# Micro_Controller.net
KiCad netlist of a schematic drawn in Altium Designer
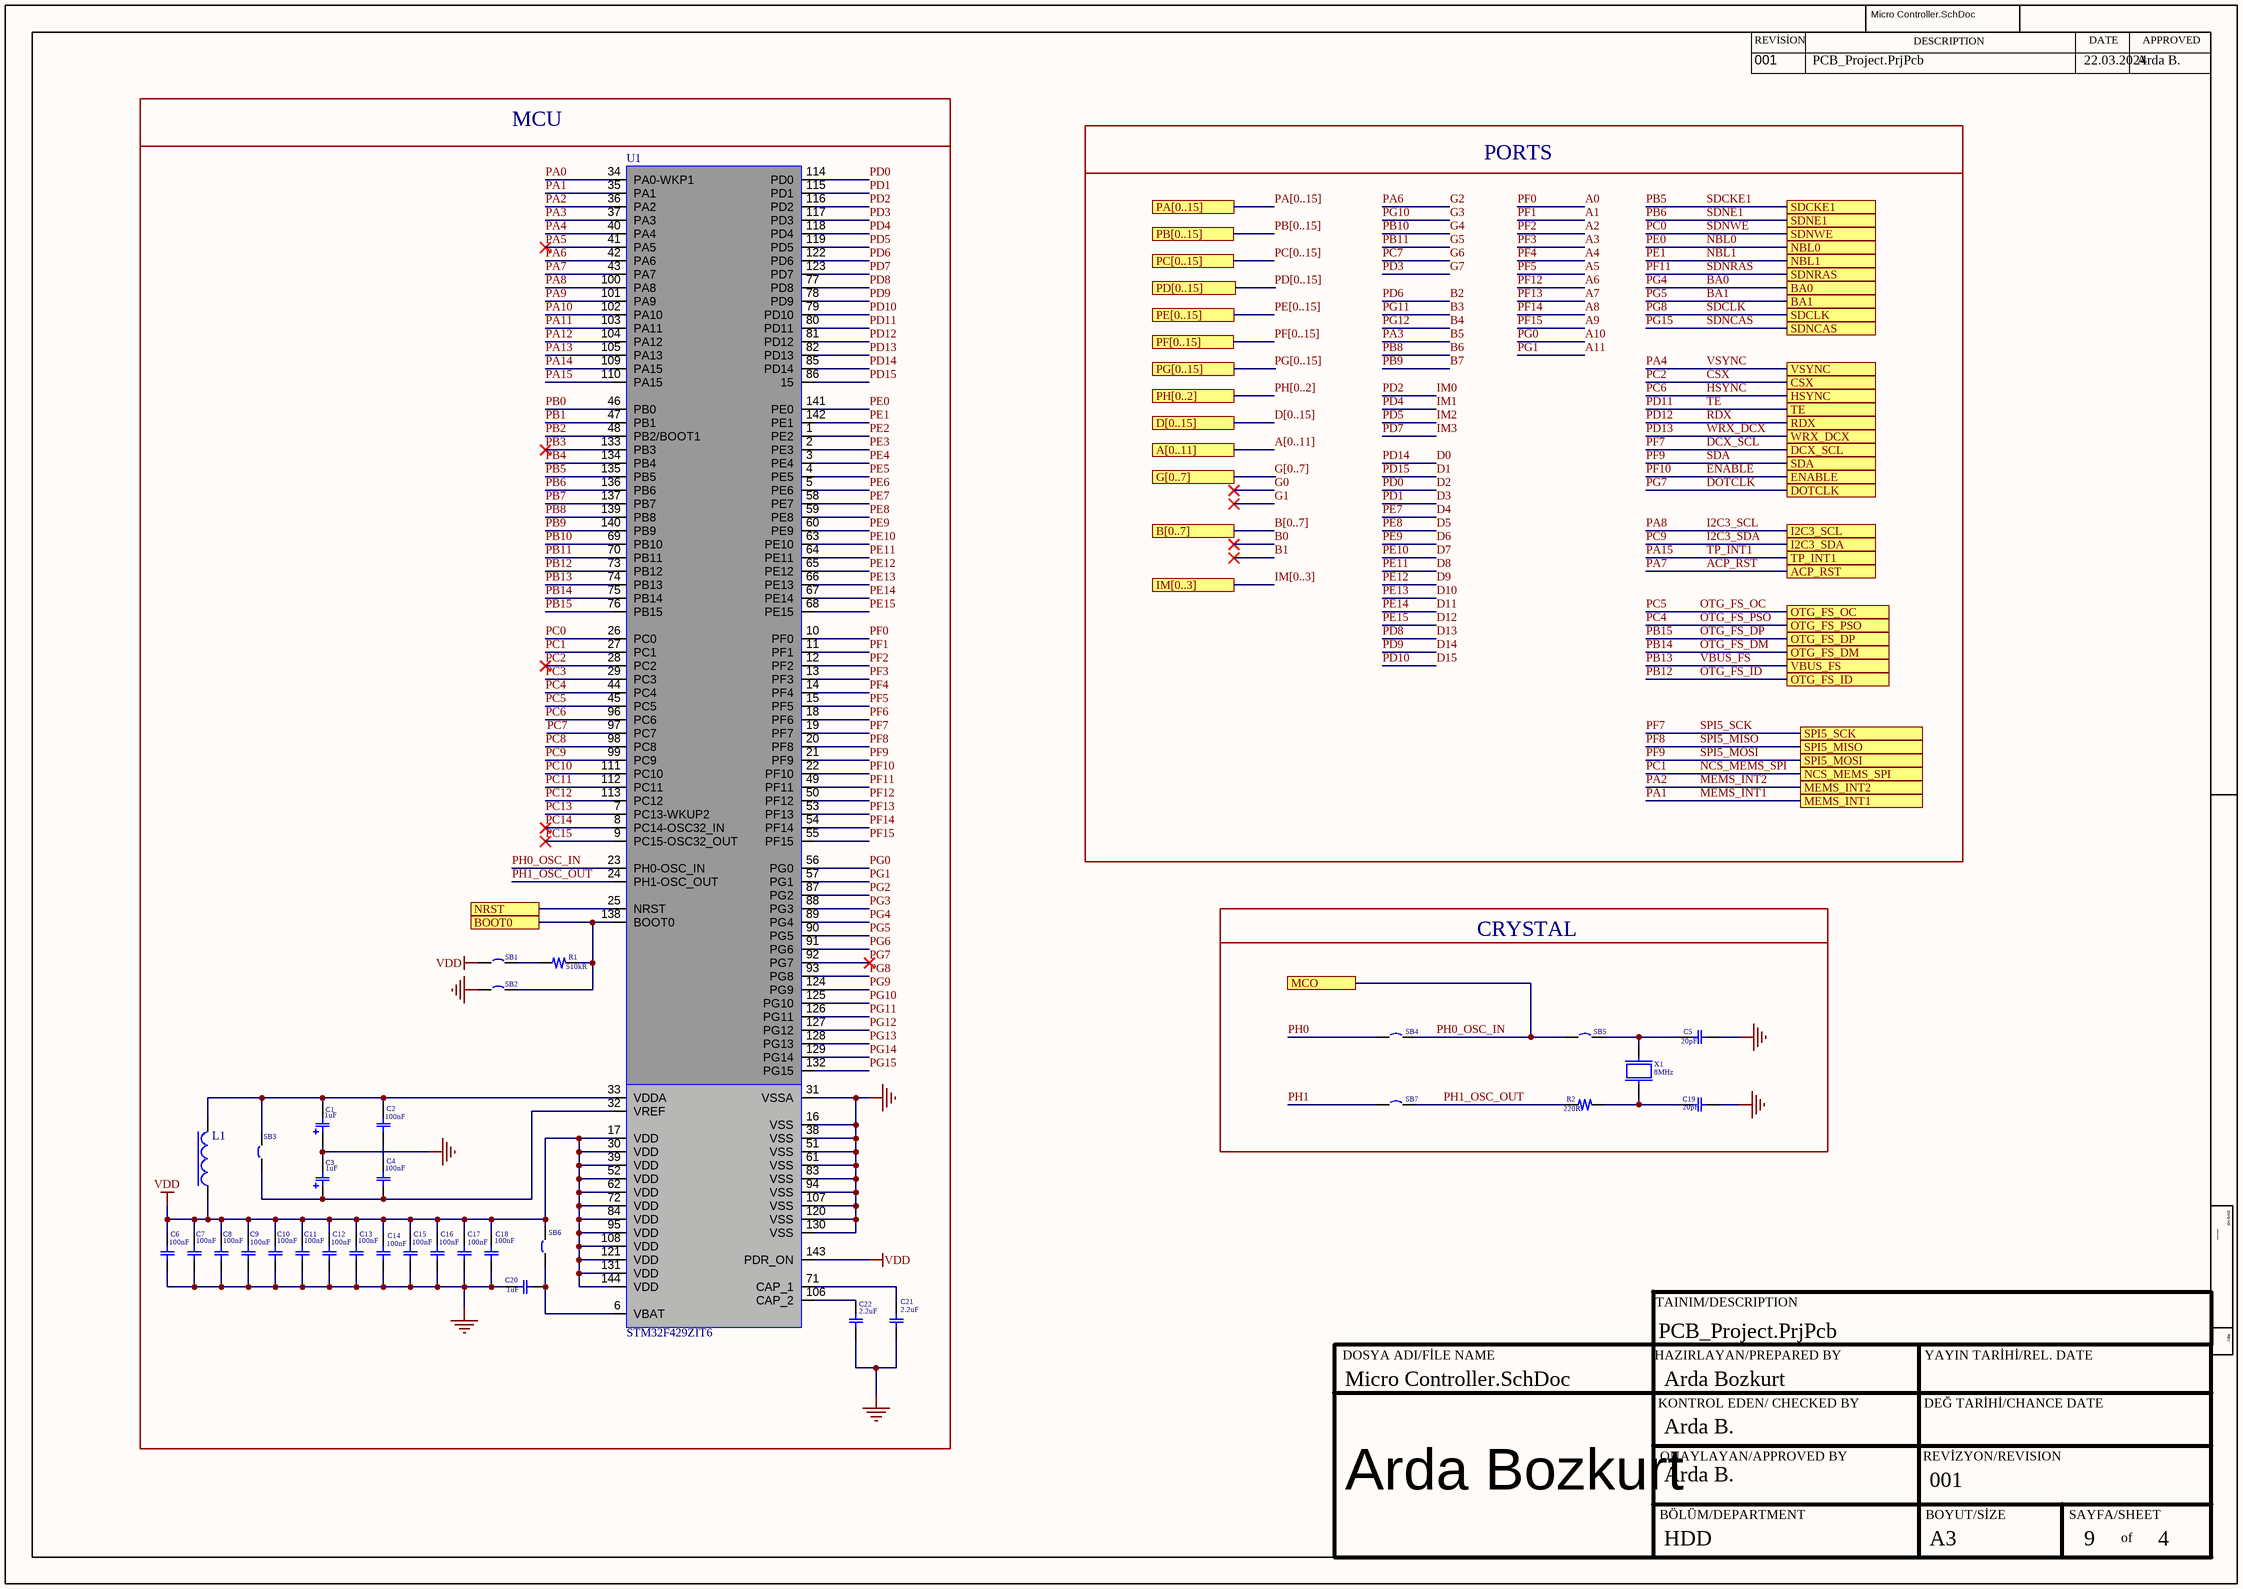
[diagram p0: Micro Controller.SchDoc]

(export (version "E")
  (design (tool "Eeschema 10.0.6"))
  (components
    (comp (ref "C1")
      (value "1uF")
      (footprint "CAP-TANT")
      (description "Cap Tant Solid 1uF 16V A CASE 10%( 3.2 X 1.6 X 1.6mm) Inward L SMD 3216-18 11 Ohm 125C T/R")
      (fields
        (field (name "MANUFACTURER") "Kyocera AVX")
        (field (name "MANUFACTURER PART NUMBER") "TAJA105K016RNJ")
      )
      (libsource (lib "STM32") (part "C-TANT 1UF 10% 16V 1206"))
    )
    (comp (ref "C2")
      (value "100nF")
      (footprint "CAP-0402")
      (description "Multilayer Ceramic Capacitor, 0.1 uF, 25 V, ± 10%, X7R, 0402 [1005 Metric]")
      (fields
        (field (name "MANUFACTURER") "Yageo")
        (field (name "MANUFACTURER PART NUMBER") "CC0402KRX7R7BB104")
      )
      (libsource (lib "STM32") (part "CAP CER 100nF 16V X7R 0402"))
    )
    (comp (ref "C3")
      (value "1uF")
      (footprint "CAP-TANT")
      (description "Cap Tant Solid 1uF 16V A CASE 10%( 3.2 X 1.6 X 1.6mm) Inward L SMD 3216-18 11 Ohm 125C T/R")
      (fields
        (field (name "MANUFACTURER") "Kyocera AVX")
        (field (name "MANUFACTURER PART NUMBER") "TAJA105K016RNJ")
      )
      (libsource (lib "STM32") (part "C-TANT 1UF 10% 16V 1206"))
    )
    (comp (ref "C4")
      (value "100nF")
      (footprint "CAP-0402")
      (description "Multilayer Ceramic Capacitor, 0.1 uF, 25 V, ± 10%, X7R, 0402 [1005 Metric]")
      (fields
        (field (name "MANUFACTURER") "Yageo")
        (field (name "MANUFACTURER PART NUMBER") "CC0402KRX7R7BB104")
      )
      (libsource (lib "STM32") (part "CAP CER 100nF 16V X7R 0402"))
    )
    (comp (ref "C5")
      (value "20pF")
      (footprint "CAP-0402")
      (description "CAP CER 20PF 50V C0G/NPO 0402")
      (fields
        (field (name "MANUFACTURER") "Yageo")
        (field (name "MANUFACTURER PART NUMBER") "CC0402JRNPO9BN200")
      )
      (libsource (lib "STM32") (part "CAP CER 20PF 50V C0G/NPO 0402"))
    )
    (comp (ref "C6")
      (value "100nF")
      (footprint "CAP-0402")
      (description "Multilayer Ceramic Capacitor, 0.1 uF, 25 V, ± 10%, X7R, 0402 [1005 Metric]")
      (fields
        (field (name "MANUFACTURER") "Yageo")
        (field (name "MANUFACTURER PART NUMBER") "CC0402KRX7R7BB104")
      )
      (libsource (lib "STM32") (part "CAP CER 100nF 16V X7R 0402"))
    )
    (comp (ref "C7")
      (value "100nF")
      (footprint "CAP-0402")
      (description "Multilayer Ceramic Capacitor, 0.1 uF, 25 V, ± 10%, X7R, 0402 [1005 Metric]")
      (fields
        (field (name "MANUFACTURER") "Yageo")
        (field (name "MANUFACTURER PART NUMBER") "CC0402KRX7R7BB104")
      )
      (libsource (lib "STM32") (part "CAP CER 100nF 16V X7R 0402"))
    )
    (comp (ref "C8")
      (value "100nF")
      (footprint "CAP-0402")
      (description "Multilayer Ceramic Capacitor, 0.1 uF, 25 V, ± 10%, X7R, 0402 [1005 Metric]")
      (fields
        (field (name "MANUFACTURER") "Yageo")
        (field (name "MANUFACTURER PART NUMBER") "CC0402KRX7R7BB104")
      )
      (libsource (lib "STM32") (part "CAP CER 100nF 16V X7R 0402"))
    )
    (comp (ref "C9")
      (value "100nF")
      (footprint "CAP-0402")
      (description "Multilayer Ceramic Capacitor, 0.1 uF, 25 V, ± 10%, X7R, 0402 [1005 Metric]")
      (fields
        (field (name "MANUFACTURER") "Yageo")
        (field (name "MANUFACTURER PART NUMBER") "CC0402KRX7R7BB104")
      )
      (libsource (lib "STM32") (part "CAP CER 100nF 16V X7R 0402"))
    )
    (comp (ref "C10")
      (value "100nF")
      (footprint "CAP-0402")
      (description "Multilayer Ceramic Capacitor, 0.1 uF, 25 V, ± 10%, X7R, 0402 [1005 Metric]")
      (fields
        (field (name "MANUFACTURER") "Yageo")
        (field (name "MANUFACTURER PART NUMBER") "CC0402KRX7R7BB104")
      )
      (libsource (lib "STM32") (part "CAP CER 100nF 16V X7R 0402"))
    )
    (comp (ref "C11")
      (value "100nF")
      (footprint "CAP-0402")
      (description "Multilayer Ceramic Capacitor, 0.1 uF, 25 V, ± 10%, X7R, 0402 [1005 Metric]")
      (fields
        (field (name "MANUFACTURER") "Yageo")
        (field (name "MANUFACTURER PART NUMBER") "CC0402KRX7R7BB104")
      )
      (libsource (lib "STM32") (part "CAP CER 100nF 16V X7R 0402"))
    )
    (comp (ref "C12")
      (value "100nF")
      (footprint "CAP-0402")
      (description "Multilayer Ceramic Capacitor, 0.1 uF, 25 V, ± 10%, X7R, 0402 [1005 Metric]")
      (fields
        (field (name "MANUFACTURER") "Yageo")
        (field (name "MANUFACTURER PART NUMBER") "CC0402KRX7R7BB104")
      )
      (libsource (lib "STM32") (part "CAP CER 100nF 16V X7R 0402"))
    )
    (comp (ref "C13")
      (value "100nF")
      (footprint "CAP-0402")
      (description "Multilayer Ceramic Capacitor, 0.1 uF, 25 V, ± 10%, X7R, 0402 [1005 Metric]")
      (fields
        (field (name "MANUFACTURER") "Yageo")
        (field (name "MANUFACTURER PART NUMBER") "CC0402KRX7R7BB104")
      )
      (libsource (lib "STM32") (part "CAP CER 100nF 16V X7R 0402"))
    )
    (comp (ref "C14")
      (value "100nF")
      (footprint "CAP-0402")
      (description "Multilayer Ceramic Capacitor, 0.1 uF, 25 V, ± 10%, X7R, 0402 [1005 Metric]")
      (fields
        (field (name "MANUFACTURER") "Yageo")
        (field (name "MANUFACTURER PART NUMBER") "CC0402KRX7R7BB104")
      )
      (libsource (lib "STM32") (part "CAP CER 100nF 16V X7R 0402"))
    )
    (comp (ref "C15")
      (value "100nF")
      (footprint "CAP-0402")
      (description "Multilayer Ceramic Capacitor, 0.1 uF, 25 V, ± 10%, X7R, 0402 [1005 Metric]")
      (fields
        (field (name "MANUFACTURER") "Yageo")
        (field (name "MANUFACTURER PART NUMBER") "CC0402KRX7R7BB104")
      )
      (libsource (lib "STM32") (part "CAP CER 100nF 16V X7R 0402"))
    )
    (comp (ref "C16")
      (value "100nF")
      (footprint "CAP-0402")
      (description "Multilayer Ceramic Capacitor, 0.1 uF, 25 V, ± 10%, X7R, 0402 [1005 Metric]")
      (fields
        (field (name "MANUFACTURER") "Yageo")
        (field (name "MANUFACTURER PART NUMBER") "CC0402KRX7R7BB104")
      )
      (libsource (lib "STM32") (part "CAP CER 100nF 16V X7R 0402"))
    )
    (comp (ref "C17")
      (value "100nF")
      (footprint "CAP-0402")
      (description "Multilayer Ceramic Capacitor, 0.1 uF, 25 V, ± 10%, X7R, 0402 [1005 Metric]")
      (fields
        (field (name "MANUFACTURER") "Yageo")
        (field (name "MANUFACTURER PART NUMBER") "CC0402KRX7R7BB104")
      )
      (libsource (lib "STM32") (part "CAP CER 100nF 16V X7R 0402"))
    )
    (comp (ref "C18")
      (value "100nF")
      (footprint "CAP-0402")
      (description "Multilayer Ceramic Capacitor, 0.1 uF, 25 V, ± 10%, X7R, 0402 [1005 Metric]")
      (fields
        (field (name "MANUFACTURER") "Yageo")
        (field (name "MANUFACTURER PART NUMBER") "CC0402KRX7R7BB104")
      )
      (libsource (lib "STM32") (part "CAP CER 100nF 16V X7R 0402"))
    )
    (comp (ref "C19")
      (value "20pF")
      (footprint "CAP-0402")
      (description "CAP CER 20PF 50V C0G/NPO 0402")
      (fields
        (field (name "MANUFACTURER") "Yageo")
        (field (name "MANUFACTURER PART NUMBER") "CC0402JRNPO9BN200")
      )
      (libsource (lib "STM32") (part "CAP CER 20PF 50V C0G/NPO 0402"))
    )
    (comp (ref "C20")
      (value "1uF")
      (footprint "CAP-0603")
      (description "Multilayer Ceramic Capacitor, 1 uF, 25 V, ± 10%, X5R, 0603 [1608 Metric]")
      (fields
        (field (name "MANUFACTURER") "Yageo")
        (field (name "MANUFACTURER PART NUMBER") "CC0603KRX5R8BB105")
      )
      (libsource (lib "STM32") (part "CAP CER 1UF 25V X5R 0603"))
    )
    (comp (ref "C21")
      (value "2.2uF")
      (footprint "CAP-1206")
      (description "Surface Mount Ceramic Multilayer Capacitor 2.2uF 10% X7R 16V 1206 Blister T/R")
      (fields
        (field (name "MANUFACTURER") "Yageo")
        (field (name "MANUFACTURER PART NUMBER") "CC1206KKX7R7BB225")
      )
      (libsource (lib "STM32") (part "CAP CER 2.2UF 16V X7R 1206"))
    )
    (comp (ref "C22")
      (value "2.2uF")
      (footprint "CAP-1206")
      (description "Surface Mount Ceramic Multilayer Capacitor 2.2uF 10% X7R 16V 1206 Blister T/R")
      (fields
        (field (name "MANUFACTURER") "Yageo")
        (field (name "MANUFACTURER PART NUMBER") "CC1206KKX7R7BB225")
      )
      (libsource (lib "STM32") (part "CAP CER 2.2UF 16V X7R 1206"))
    )
    (comp (ref "L1")
      (value "FCM 1608KF-301T05")
      (footprint "FB-0603")
      (description "500mA 1 350mΩ 300Ω@100MHz ±25% 0603 Ferrite Beads ROHS")
      (fields
        (field (name "MANUFACTURER") "Tai Tech")
        (field (name "MANUFACTURER PART NUMBER") "FCM1608KF-301T05")
      )
      (libsource (lib "STM32") (part "FB 300 OHMS @ 100 MHZ 1 POWER, SIGN"))
    )
    (comp (ref "R1")
      (value "510kR")
      (footprint "RES-0402")
      (description "SMD Chip Resistor, 510 kOhm, ± 1%, 63 mW, 0402 [1005 Metric], Thick Film, General Purpose")
      (fields
        (field (name "MANUFACTURER") "Yageo")
        (field (name "MANUFACTURER PART NUMBER") "RC0402FR-07510KL")
      )
      (libsource (lib "STM32") (part "RES 510K OHM 1% 1/16W 0402"))
    )
    (comp (ref "R2")
      (value "220R")
      (footprint "RES-0402")
      (description "SMD Chip Resistor, 220 Ohm, ± 1%, 63 mW, 0402 [1005 Metric], Thick Film, General Purpose")
      (fields
        (field (name "MANUFACTURER") "Yageo")
        (field (name "MANUFACTURER PART NUMBER") "RC0402FR-07220RL")
      )
      (libsource (lib "STM32") (part "RES 220 OHM 1% 1/16W 0402"))
    )
    (comp (ref "SB1")
      (value "RC0402JR-070RL")
      (footprint "RES-0402")
      (description "Zero Ohm Resistor, Jumper, 0402 [1005 Metric], Thick Film, 62.5 mW, 1 A, Surface Mount")
      (fields
        (field (name "MANUFACTURER") "Yageo")
        (field (name "MANUFACTURER PART NUMBER") "RC0603JR-070RL")
      )
      (libsource (lib "STM32") (part "RES 0 OHM JUMPER 1/10W 0603"))
    )
    (comp (ref "SB2")
      (value "RC0402JR-070RL")
      (footprint "RES-0402")
      (description "Zero Ohm Resistor, Jumper, 0402 [1005 Metric], Thick Film, 62.5 mW, 1 A, Surface Mount")
      (fields
        (field (name "MANUFACTURER") "Yageo")
        (field (name "MANUFACTURER PART NUMBER") "RC0603JR-070RL")
      )
      (libsource (lib "STM32") (part "RES 0 OHM JUMPER 1/10W 0603"))
    )
    (comp (ref "SB3")
      (value "RC0402JR-070RL")
      (footprint "RES-0402")
      (description "Zero Ohm Resistor, Jumper, 0402 [1005 Metric], Thick Film, 62.5 mW, 1 A, Surface Mount")
      (fields
        (field (name "MANUFACTURER") "Yageo")
        (field (name "MANUFACTURER PART NUMBER") "RC0603JR-070RL")
      )
      (libsource (lib "") (part "RES 0 OHM JUMPER 1/10W 0603_1"))
    )
    (comp (ref "SB4")
      (value "RC0402JR-070RL")
      (footprint "RES-0402")
      (description "Zero Ohm Resistor, Jumper, 0402 [1005 Metric], Thick Film, 62.5 mW, 1 A, Surface Mount")
      (fields
        (field (name "MANUFACTURER") "Yageo")
        (field (name "MANUFACTURER PART NUMBER") "RC0603JR-070RL")
      )
      (libsource (lib "STM32") (part "RES 0 OHM JUMPER 1/10W 0603"))
    )
    (comp (ref "SB5")
      (value "RC0402JR-070RL")
      (footprint "RES-0402")
      (description "Zero Ohm Resistor, Jumper, 0402 [1005 Metric], Thick Film, 62.5 mW, 1 A, Surface Mount")
      (fields
        (field (name "MANUFACTURER") "Yageo")
        (field (name "MANUFACTURER PART NUMBER") "RC0603JR-070RL")
      )
      (libsource (lib "STM32") (part "RES 0 OHM JUMPER 1/10W 0603"))
    )
    (comp (ref "SB6")
      (value "RC0402JR-070RL")
      (footprint "RES-0402")
      (description "Zero Ohm Resistor, Jumper, 0402 [1005 Metric], Thick Film, 62.5 mW, 1 A, Surface Mount")
      (fields
        (field (name "MANUFACTURER") "Yageo")
        (field (name "MANUFACTURER PART NUMBER") "RC0603JR-070RL")
      )
      (libsource (lib "") (part "RES 0 OHM JUMPER 1/10W 0603_1"))
    )
    (comp (ref "SB7")
      (value "RC0402JR-070RL")
      (footprint "RES-0402")
      (description "Zero Ohm Resistor, Jumper, 0402 [1005 Metric], Thick Film, 62.5 mW, 1 A, Surface Mount")
      (fields
        (field (name "MANUFACTURER") "Yageo")
        (field (name "MANUFACTURER PART NUMBER") "RC0603JR-070RL")
      )
      (libsource (lib "STM32") (part "RES 0 OHM JUMPER 1/10W 0603"))
    )
    (comp (ref "U1")
      (value "STM32F429ZIT6")
      (footprint "LQFP-144")
      (description "RISC Microcontroller, 32-Bit, FLASH, CORTEX-M4F CPU, 180MHz, CMOS, PQFP144")
      (fields (field (name "MANUFACTURER") "STMicroelectronics"))
      (libsource (lib "STM32") (part "IC MCU 32BIT 2MB FLASH 144LQFP"))
    )
    (comp (ref "X1")
      (value "H1OED8K5SC-112YXC-8M")
      (footprint "HC-49US")
      (description "HC-49US 8MHZ 20PF 20PPM H1OED8K5")
      (fields (field (name "MANUFACTURER") "YXC") (field (name "FREQUENCY") "8MHz"))
      (libsource (lib "STM32") (part "Crystal 8MHZ 20PF 20PPM H1OED8K5"))
    )
  )
  (nets
    (net (code "5") (name "/B2") (class "Default")
      (node (ref "U1") (pin "122") (pinfunction "PD6_122") (pintype "passive"))
    )
    (net (code "6") (name "/B3") (class "Default")
      (node (ref "U1") (pin "126") (pinfunction "PG11_126") (pintype "passive"))
    )
    (net (code "7") (name "/B4") (class "Default")
      (node (ref "U1") (pin "127") (pinfunction "PG12_127") (pintype "passive"))
    )
    (net (code "8") (name "/BOOT0") (class "Default")
      (node (ref "R1") (pin "2") (pinfunction "2_2") (pintype "passive"))
      (node (ref "SB2") (pin "2") (pinfunction "2_2") (pintype "passive"))
      (node (ref "U1") (pin "138") (pinfunction "BOOT0_138") (pintype "passive"))
    )
    (net (code "10") (name "/D0") (class "Default")
      (node (ref "U1") (pin "85") (pinfunction "PD14_85") (pintype "passive"))
    )
    (net (code "11") (name "/D1") (class "Default")
      (node (ref "U1") (pin "86") (pinfunction "15_86") (pintype "passive"))
    )
    (net (code "12") (name "/D2") (class "Default")
      (node (ref "U1") (pin "114") (pinfunction "PD0_114") (pintype "passive"))
    )
    (net (code "13") (name "/D3") (class "Default")
      (node (ref "U1") (pin "115") (pinfunction "PD1_115") (pintype "passive"))
    )
    (net (code "14") (name "/D4") (class "Default")
      (node (ref "U1") (pin "58") (pinfunction "PE7_58") (pintype "passive"))
    )
    (net (code "15") (name "/D5") (class "Default")
      (node (ref "U1") (pin "59") (pinfunction "PE8_59") (pintype "passive"))
    )
    (net (code "16") (name "/D6") (class "Default")
      (node (ref "U1") (pin "60") (pinfunction "PE9_60") (pintype "passive"))
    )
    (net (code "17") (name "/D7") (class "Default")
      (node (ref "U1") (pin "63") (pinfunction "PE10_63") (pintype "passive"))
    )
    (net (code "18") (name "/D8") (class "Default")
      (node (ref "U1") (pin "64") (pinfunction "PE11_64") (pintype "passive"))
    )
    (net (code "19") (name "/D9") (class "Default")
      (node (ref "U1") (pin "65") (pinfunction "PE12_65") (pintype "passive"))
    )
    (net (code "20") (name "/D10") (class "Default")
      (node (ref "U1") (pin "66") (pinfunction "PE13_66") (pintype "passive"))
    )
    (net (code "21") (name "/D11") (class "Default")
      (node (ref "U1") (pin "67") (pinfunction "PE14_67") (pintype "passive"))
    )
    (net (code "22") (name "/D12") (class "Default")
      (node (ref "U1") (pin "68") (pinfunction "PE15_68") (pintype "passive"))
    )
    (net (code "23") (name "/D13") (class "Default")
      (node (ref "U1") (pin "77") (pinfunction "PD8_77") (pintype "passive"))
    )
    (net (code "24") (name "/D14") (class "Default")
      (node (ref "U1") (pin "78") (pinfunction "PD9_78") (pintype "passive"))
    )
    (net (code "25") (name "/D15") (class "Default")
      (node (ref "U1") (pin "79") (pinfunction "PD10_79") (pintype "passive"))
    )
    (net (code "30") (name "/IM0") (class "Default")
      (node (ref "U1") (pin "116") (pinfunction "PD2_116") (pintype "passive"))
    )
    (net (code "31") (name "/IM1") (class "Default")
      (node (ref "U1") (pin "118") (pinfunction "PD4_118") (pintype "passive"))
    )
    (net (code "32") (name "/IM2") (class "Default")
      (node (ref "U1") (pin "119") (pinfunction "PD5_119") (pintype "passive"))
    )
    (net (code "33") (name "/IM3") (class "Default")
      (node (ref "U1") (pin "123") (pinfunction "PD7_123") (pintype "passive"))
    )
    (net (code "35") (name "/NRST") (class "Default")
      (node (ref "U1") (pin "25") (pinfunction "NRST_25") (pintype "passive"))
    )
    (net (code "36") (name "/PA0") (class "Default")
      (node (ref "U1") (pin "34") (pinfunction "PA0-WKP1_34") (pintype "passive"))
    )
    (net (code "37") (name "/PA1") (class "Default")
      (node (ref "U1") (pin "35") (pinfunction "PA1_35") (pintype "passive"))
    )
    (net (code "38") (name "/PA2") (class "Default")
      (node (ref "U1") (pin "36") (pinfunction "PA2_36") (pintype "passive"))
    )
    (net (code "39") (name "/PA3") (class "Default")
      (node (ref "U1") (pin "37") (pinfunction "PA3_37") (pintype "passive"))
    )
    (net (code "40") (name "/PA4") (class "Default")
      (node (ref "U1") (pin "40") (pinfunction "PA4_40") (pintype "passive"))
    )
    (net (code "41") (name "/PA5") (class "Default")
      (node (ref "U1") (pin "41") (pinfunction "PA5_41") (pintype "passive+no_connect"))
    )
    (net (code "42") (name "/PA6") (class "Default")
      (node (ref "U1") (pin "42") (pinfunction "PA6_42") (pintype "passive"))
    )
    (net (code "43") (name "/PA7") (class "Default")
      (node (ref "U1") (pin "43") (pinfunction "PA7_43") (pintype "passive"))
    )
    (net (code "44") (name "/PA8") (class "Default")
      (node (ref "U1") (pin "100") (pinfunction "PA8_100") (pintype "passive"))
    )
    (net (code "45") (name "/PA9") (class "Default")
      (node (ref "U1") (pin "101") (pinfunction "PA9_101") (pintype "passive"))
    )
    (net (code "46") (name "/PA10") (class "Default")
      (node (ref "U1") (pin "102") (pinfunction "PA10_102") (pintype "passive"))
    )
    (net (code "47") (name "/PA11") (class "Default")
      (node (ref "U1") (pin "103") (pinfunction "PA11_103") (pintype "passive"))
    )
    (net (code "48") (name "/PA12") (class "Default")
      (node (ref "U1") (pin "104") (pinfunction "PA12_104") (pintype "passive"))
    )
    (net (code "49") (name "/PA13") (class "Default")
      (node (ref "U1") (pin "105") (pinfunction "PA13_105") (pintype "passive"))
    )
    (net (code "50") (name "/PA14") (class "Default")
      (node (ref "U1") (pin "109") (pinfunction "PA15_109") (pintype "passive"))
    )
    (net (code "51") (name "/PA15") (class "Default")
      (node (ref "U1") (pin "110") (pinfunction "PA15_110") (pintype "passive"))
    )
    (net (code "53") (name "/PB0") (class "Default")
      (node (ref "U1") (pin "46") (pinfunction "PB0_46") (pintype "passive"))
    )
    (net (code "54") (name "/PB1") (class "Default")
      (node (ref "U1") (pin "47") (pinfunction "PB1_47") (pintype "passive"))
    )
    (net (code "55") (name "/PB2") (class "Default")
      (node (ref "U1") (pin "48") (pinfunction "PB2/BOOT1_48") (pintype "passive"))
    )
    (net (code "56") (name "/PB3") (class "Default")
      (node (ref "U1") (pin "133") (pinfunction "PB3_133") (pintype "passive+no_connect"))
    )
    (net (code "57") (name "/PB4") (class "Default")
      (node (ref "U1") (pin "134") (pinfunction "PB4_134") (pintype "passive"))
    )
    (net (code "58") (name "/PB5") (class "Default")
      (node (ref "U1") (pin "135") (pinfunction "PB5_135") (pintype "passive"))
    )
    (net (code "59") (name "/PB6") (class "Default")
      (node (ref "U1") (pin "136") (pinfunction "PB6_136") (pintype "passive"))
    )
    (net (code "60") (name "/PB7") (class "Default")
      (node (ref "U1") (pin "137") (pinfunction "PB7_137") (pintype "passive"))
    )
    (net (code "61") (name "/PB8") (class "Default")
      (node (ref "U1") (pin "139") (pinfunction "PB8_139") (pintype "passive"))
    )
    (net (code "62") (name "/PB9") (class "Default")
      (node (ref "U1") (pin "140") (pinfunction "PB9_140") (pintype "passive"))
    )
    (net (code "63") (name "/PB10") (class "Default")
      (node (ref "U1") (pin "69") (pinfunction "PB10_69") (pintype "passive"))
    )
    (net (code "64") (name "/PB11") (class "Default")
      (node (ref "U1") (pin "70") (pinfunction "PB11_70") (pintype "passive"))
    )
    (net (code "65") (name "/PB12") (class "Default")
      (node (ref "U1") (pin "73") (pinfunction "PB12_73") (pintype "passive"))
    )
    (net (code "66") (name "/PB13") (class "Default")
      (node (ref "U1") (pin "74") (pinfunction "PB13_74") (pintype "passive"))
    )
    (net (code "67") (name "/PB14") (class "Default")
      (node (ref "U1") (pin "75") (pinfunction "PB14_75") (pintype "passive"))
    )
    (net (code "68") (name "/PB15") (class "Default")
      (node (ref "U1") (pin "76") (pinfunction "PB15_76") (pintype "passive"))
    )
    (net (code "70") (name "/PC0") (class "Default")
      (node (ref "U1") (pin "26") (pinfunction "PC0_26") (pintype "passive"))
    )
    (net (code "71") (name "/PC1") (class "Default")
      (node (ref "U1") (pin "27") (pinfunction "PC1_27") (pintype "passive"))
    )
    (net (code "72") (name "/PC2") (class "Default")
      (node (ref "U1") (pin "28") (pinfunction "PC2_28") (pintype "passive+no_connect"))
    )
    (net (code "73") (name "/PC3") (class "Default")
      (node (ref "U1") (pin "29") (pinfunction "PC3_29") (pintype "passive"))
    )
    (net (code "74") (name "/PC4") (class "Default")
      (node (ref "U1") (pin "44") (pinfunction "PC4_44") (pintype "passive"))
    )
    (net (code "75") (name "/PC5") (class "Default")
      (node (ref "U1") (pin "45") (pinfunction "PC5_45") (pintype "passive"))
    )
    (net (code "76") (name "/PC6") (class "Default")
      (node (ref "U1") (pin "96") (pinfunction "PC6_96") (pintype "passive"))
    )
    (net (code "77") (name "/PC7") (class "Default")
      (node (ref "U1") (pin "97") (pinfunction "PC7_97") (pintype "passive"))
    )
    (net (code "78") (name "/PC8") (class "Default")
      (node (ref "U1") (pin "98") (pinfunction "PC8_98") (pintype "passive"))
    )
    (net (code "79") (name "/PC9") (class "Default")
      (node (ref "U1") (pin "99") (pinfunction "PC9_99") (pintype "passive"))
    )
    (net (code "80") (name "/PC10") (class "Default")
      (node (ref "U1") (pin "111") (pinfunction "PC10_111") (pintype "passive"))
    )
    (net (code "81") (name "/PC11") (class "Default")
      (node (ref "U1") (pin "112") (pinfunction "PC11_112") (pintype "passive"))
    )
    (net (code "82") (name "/PC12") (class "Default")
      (node (ref "U1") (pin "113") (pinfunction "PC12_113") (pintype "passive"))
    )
    (net (code "83") (name "/PC13") (class "Default")
      (node (ref "U1") (pin "7") (pinfunction "PC13-WKUP2_7") (pintype "passive"))
    )
    (net (code "84") (name "/PC14") (class "Default")
      (node (ref "U1") (pin "8") (pinfunction "PC14-OSC32_IN_8") (pintype "passive+no_connect"))
    )
    (net (code "85") (name "/PC15") (class "Default")
      (node (ref "U1") (pin "9") (pinfunction "PC15-OSC32_OUT_9") (pintype "passive+no_connect"))
    )
    (net (code "87") (name "/PD3") (class "Default")
      (node (ref "U1") (pin "117") (pinfunction "PD3_117") (pintype "passive"))
    )
    (net (code "88") (name "/PD11") (class "Default")
      (node (ref "U1") (pin "80") (pinfunction "PD11_80") (pintype "passive"))
    )
    (net (code "89") (name "/PD12") (class "Default")
      (node (ref "U1") (pin "81") (pinfunction "PD12_81") (pintype "passive"))
    )
    (net (code "90") (name "/PD13") (class "Default")
      (node (ref "U1") (pin "82") (pinfunction "PD13_82") (pintype "passive"))
    )
    (net (code "92") (name "/PE0") (class "Default")
      (node (ref "U1") (pin "141") (pinfunction "PE0_141") (pintype "passive"))
    )
    (net (code "93") (name "/PE1") (class "Default")
      (node (ref "U1") (pin "142") (pinfunction "PE1_142") (pintype "passive"))
    )
    (net (code "94") (name "/PE2") (class "Default")
      (node (ref "U1") (pin "1") (pinfunction "PE2_1") (pintype "passive"))
    )
    (net (code "95") (name "/PE3") (class "Default")
      (node (ref "U1") (pin "2") (pinfunction "PE3_2") (pintype "passive"))
    )
    (net (code "96") (name "/PE4") (class "Default")
      (node (ref "U1") (pin "3") (pinfunction "PE4_3") (pintype "passive"))
    )
    (net (code "97") (name "/PE5") (class "Default")
      (node (ref "U1") (pin "4") (pinfunction "PE5_4") (pintype "passive"))
    )
    (net (code "98") (name "/PE6") (class "Default")
      (node (ref "U1") (pin "5") (pinfunction "PE6_5") (pintype "passive"))
    )
    (net (code "100") (name "/PF0") (class "Default")
      (node (ref "U1") (pin "10") (pinfunction "PF0_10") (pintype "passive"))
    )
    (net (code "101") (name "/PF1") (class "Default")
      (node (ref "U1") (pin "11") (pinfunction "PF1_11") (pintype "passive"))
    )
    (net (code "102") (name "/PF2") (class "Default")
      (node (ref "U1") (pin "12") (pinfunction "PF2_12") (pintype "passive"))
    )
    (net (code "103") (name "/PF3") (class "Default")
      (node (ref "U1") (pin "13") (pinfunction "PF3_13") (pintype "passive"))
    )
    (net (code "104") (name "/PF4") (class "Default")
      (node (ref "U1") (pin "14") (pinfunction "PF4_14") (pintype "passive"))
    )
    (net (code "105") (name "/PF5") (class "Default")
      (node (ref "U1") (pin "15") (pinfunction "PF5_15") (pintype "passive"))
    )
    (net (code "106") (name "/PF6") (class "Default")
      (node (ref "U1") (pin "18") (pinfunction "PF6_18") (pintype "passive"))
    )
    (net (code "107") (name "/PF7") (class "Default")
      (node (ref "U1") (pin "19") (pinfunction "PF7_19") (pintype "passive"))
    )
    (net (code "108") (name "/PF8") (class "Default")
      (node (ref "U1") (pin "20") (pinfunction "PF8_20") (pintype "passive"))
    )
    (net (code "109") (name "/PF9") (class "Default")
      (node (ref "U1") (pin "21") (pinfunction "PF9_21") (pintype "passive"))
    )
    (net (code "110") (name "/PF10") (class "Default")
      (node (ref "U1") (pin "22") (pinfunction "PF10_22") (pintype "passive"))
    )
    (net (code "111") (name "/PF11") (class "Default")
      (node (ref "U1") (pin "49") (pinfunction "PF11_49") (pintype "passive"))
    )
    (net (code "112") (name "/PF12") (class "Default")
      (node (ref "U1") (pin "50") (pinfunction "PF12_50") (pintype "passive"))
    )
    (net (code "113") (name "/PF13") (class "Default")
      (node (ref "U1") (pin "53") (pinfunction "PF13_53") (pintype "passive"))
    )
    (net (code "114") (name "/PF14") (class "Default")
      (node (ref "U1") (pin "54") (pinfunction "PF14_54") (pintype "passive"))
    )
    (net (code "115") (name "/PF15") (class "Default")
      (node (ref "U1") (pin "55") (pinfunction "PF15_55") (pintype "passive"))
    )
    (net (code "117") (name "/PG0") (class "Default")
      (node (ref "U1") (pin "56") (pinfunction "PG0_56") (pintype "passive"))
    )
    (net (code "118") (name "/PG1") (class "Default")
      (node (ref "U1") (pin "57") (pinfunction "PG1_57") (pintype "passive"))
    )
    (net (code "119") (name "/PG2") (class "Default")
      (node (ref "U1") (pin "87") (pinfunction "PG2_87") (pintype "passive"))
    )
    (net (code "120") (name "/PG3") (class "Default")
      (node (ref "U1") (pin "88") (pinfunction "PG3_88") (pintype "passive"))
    )
    (net (code "121") (name "/PG4") (class "Default")
      (node (ref "U1") (pin "89") (pinfunction "PG4_89") (pintype "passive"))
    )
    (net (code "122") (name "/PG5") (class "Default")
      (node (ref "U1") (pin "90") (pinfunction "PG5_90") (pintype "passive"))
    )
    (net (code "123") (name "/PG6") (class "Default")
      (node (ref "U1") (pin "91") (pinfunction "PG6_91") (pintype "passive"))
    )
    (net (code "124") (name "/PG7") (class "Default")
      (node (ref "U1") (pin "92") (pinfunction "PG7_92") (pintype "passive+no_connect"))
    )
    (net (code "125") (name "/PG8") (class "Default")
      (node (ref "U1") (pin "93") (pinfunction "PG8_93") (pintype "passive"))
    )
    (net (code "126") (name "/PG9") (class "Default")
      (node (ref "U1") (pin "124") (pinfunction "PG9_124") (pintype "passive"))
    )
    (net (code "127") (name "/PG10") (class "Default")
      (node (ref "U1") (pin "125") (pinfunction "PG10_125") (pintype "passive"))
    )
    (net (code "128") (name "/PG13") (class "Default")
      (node (ref "U1") (pin "128") (pinfunction "PG13_128") (pintype "passive"))
    )
    (net (code "129") (name "/PG14") (class "Default")
      (node (ref "U1") (pin "129") (pinfunction "PG14_129") (pintype "passive"))
    )
    (net (code "130") (name "/PG15") (class "Default")
      (node (ref "U1") (pin "132") (pinfunction "PG15_132") (pintype "passive"))
    )
    (net (code "132") (name "/PH0") (class "Default")
      (node (ref "SB4") (pin "1") (pinfunction "1_1") (pintype "passive"))
    )
    (net (code "133") (name "/PH0_OSC_IN") (class "Default")
      (node (ref "SB4") (pin "2") (pinfunction "2_2") (pintype "passive"))
      (node (ref "SB5") (pin "1") (pinfunction "1_1") (pintype "passive"))
      (node (ref "U1") (pin "23") (pinfunction "PH0-OSC_IN_23") (pintype "passive"))
    )
    (net (code "134") (name "/PH1") (class "Default")
      (node (ref "SB7") (pin "1") (pinfunction "1_1") (pintype "passive"))
    )
    (net (code "135") (name "/PH1_OSC_OUT") (class "Default")
      (node (ref "R2") (pin "1") (pinfunction "1_1") (pintype "passive"))
      (node (ref "SB7") (pin "2") (pinfunction "2_2") (pintype "passive"))
      (node (ref "U1") (pin "24") (pinfunction "PH1-OSC_OUT_24") (pintype "passive"))
    )
    (net (code "137") (name "GND") (class "Default")
      (node (ref "C1") (pin "1") (pinfunction "1_1") (pintype "passive"))
      (node (ref "C10") (pin "1") (pinfunction "1_1") (pintype "passive"))
      (node (ref "C11") (pin "1") (pinfunction "1_1") (pintype "passive"))
      (node (ref "C12") (pin "1") (pinfunction "1_1") (pintype "passive"))
      (node (ref "C13") (pin "1") (pinfunction "1_1") (pintype "passive"))
      (node (ref "C14") (pin "1") (pinfunction "1_1") (pintype "passive"))
      (node (ref "C15") (pin "1") (pinfunction "1_1") (pintype "passive"))
      (node (ref "C16") (pin "1") (pinfunction "1_1") (pintype "passive"))
      (node (ref "C17") (pin "1") (pinfunction "1_1") (pintype "passive"))
      (node (ref "C18") (pin "1") (pinfunction "1_1") (pintype "passive"))
      (node (ref "C19") (pin "2") (pinfunction "2_2") (pintype "passive"))
      (node (ref "C20") (pin "1") (pinfunction "1_1") (pintype "passive"))
      (node (ref "C21") (pin "1") (pinfunction "1_1") (pintype "passive"))
      (node (ref "C22") (pin "1") (pinfunction "1_1") (pintype "passive"))
      (node (ref "C3") (pin "2") (pinfunction "2_2") (pintype "passive"))
      (node (ref "C5") (pin "2") (pinfunction "2_2") (pintype "passive"))
      (node (ref "C6") (pin "1") (pinfunction "1_1") (pintype "passive"))
      (node (ref "C7") (pin "1") (pinfunction "1_1") (pintype "passive"))
      (node (ref "C8") (pin "1") (pinfunction "1_1") (pintype "passive"))
      (node (ref "C9") (pin "1") (pinfunction "1_1") (pintype "passive"))
      (node (ref "SB2") (pin "1") (pinfunction "1_1") (pintype "passive"))
      (node (ref "U1") (pin "107") (pinfunction "VSS_107") (pintype "passive"))
      (node (ref "U1") (pin "120") (pinfunction "VSS_120") (pintype "passive"))
      (node (ref "U1") (pin "130") (pinfunction "VSS_130") (pintype "passive"))
      (node (ref "U1") (pin "16") (pinfunction "VSS_16") (pintype "passive"))
      (node (ref "U1") (pin "31") (pinfunction "VSSA_31") (pintype "passive"))
      (node (ref "U1") (pin "38") (pinfunction "VSS_38") (pintype "passive"))
      (node (ref "U1") (pin "51") (pinfunction "VSS_51") (pintype "passive"))
      (node (ref "U1") (pin "61") (pinfunction "VSS_61") (pintype "passive"))
      (node (ref "U1") (pin "83") (pinfunction "VSS_83") (pintype "passive"))
      (node (ref "U1") (pin "94") (pinfunction "VSS_94") (pintype "passive"))
    )
    (net (code "138") (name "Net-(C2-Pad1)") (class "Default")
      (node (ref "C2") (pin "1") (pinfunction "1_1") (pintype "passive"))
      (node (ref "C4") (pin "2") (pinfunction "2_2") (pintype "passive"))
    )
    (net (code "139") (name "Net-(C5-Pad1)") (class "Default")
      (node (ref "C5") (pin "1") (pinfunction "1_1") (pintype "passive"))
      (node (ref "SB5") (pin "2") (pinfunction "2_2") (pintype "passive"))
      (node (ref "X1") (pin "2") (pinfunction "2_2") (pintype "passive"))
    )
    (net (code "140") (name "Net-(C19-Pad1)") (class "Default")
      (node (ref "C19") (pin "1") (pinfunction "1_1") (pintype "passive"))
      (node (ref "R2") (pin "2") (pinfunction "2_2") (pintype "passive"))
      (node (ref "X1") (pin "1") (pinfunction "1_1") (pintype "passive"))
    )
    (net (code "141") (name "Net-(R1-Pad1)") (class "Default")
      (node (ref "R1") (pin "1") (pinfunction "1_1") (pintype "passive"))
      (node (ref "SB1") (pin "2") (pinfunction "2_2") (pintype "passive"))
    )
    (net (code "142") (name "Net-(U1-CAP_1)") (class "Default")
      (node (ref "C21") (pin "2") (pinfunction "2_2") (pintype "passive"))
      (node (ref "U1") (pin "71") (pinfunction "CAP_1_71") (pintype "passive"))
    )
    (net (code "143") (name "Net-(U1-CAP_2)") (class "Default")
      (node (ref "C22") (pin "2") (pinfunction "2_2") (pintype "passive"))
      (node (ref "U1") (pin "106") (pinfunction "CAP_2_106") (pintype "passive"))
    )
    (net (code "144") (name "Net-(U1-VBAT)") (class "Default")
      (node (ref "C20") (pin "2") (pinfunction "2_2") (pintype "passive"))
      (node (ref "SB6") (pin "1") (pinfunction "1_1") (pintype "passive"))
      (node (ref "U1") (pin "6") (pinfunction "VBAT_6") (pintype "passive"))
    )
    (net (code "145") (name "Net-(U1-VDDA)") (class "Default")
      (node (ref "C1") (pin "2") (pinfunction "2_2") (pintype "passive"))
      (node (ref "C2") (pin "2") (pinfunction "2_2") (pintype "passive"))
      (node (ref "L1") (pin "2") (pinfunction "2_2") (pintype "passive"))
      (node (ref "SB3") (pin "2") (pinfunction "2_2") (pintype "passive"))
      (node (ref "U1") (pin "33") (pinfunction "VDDA_33") (pintype "passive"))
    )
    (net (code "146") (name "Net-(U1-VREF)") (class "Default")
      (node (ref "C3") (pin "1") (pinfunction "1_1") (pintype "passive"))
      (node (ref "C4") (pin "1") (pinfunction "1_1") (pintype "passive"))
      (node (ref "SB3") (pin "1") (pinfunction "1_1") (pintype "passive"))
      (node (ref "U1") (pin "32") (pinfunction "VREF_32") (pintype "passive"))
    )
    (net (code "147") (name "VDD") (class "Default")
      (node (ref "C10") (pin "2") (pinfunction "2_2") (pintype "passive"))
      (node (ref "C11") (pin "2") (pinfunction "2_2") (pintype "passive"))
      (node (ref "C12") (pin "2") (pinfunction "2_2") (pintype "passive"))
      (node (ref "C13") (pin "2") (pinfunction "2_2") (pintype "passive"))
      (node (ref "C14") (pin "2") (pinfunction "2_2") (pintype "passive"))
      (node (ref "C15") (pin "2") (pinfunction "2_2") (pintype "passive"))
      (node (ref "C16") (pin "2") (pinfunction "2_2") (pintype "passive"))
      (node (ref "C17") (pin "2") (pinfunction "2_2") (pintype "passive"))
      (node (ref "C18") (pin "2") (pinfunction "2_2") (pintype "passive"))
      (node (ref "C6") (pin "2") (pinfunction "2_2") (pintype "passive"))
      (node (ref "C7") (pin "2") (pinfunction "2_2") (pintype "passive"))
      (node (ref "C8") (pin "2") (pinfunction "2_2") (pintype "passive"))
      (node (ref "C9") (pin "2") (pinfunction "2_2") (pintype "passive"))
      (node (ref "L1") (pin "1") (pinfunction "1_1") (pintype "passive"))
      (node (ref "SB1") (pin "1") (pinfunction "1_1") (pintype "passive"))
      (node (ref "SB6") (pin "2") (pinfunction "2_2") (pintype "passive"))
      (node (ref "U1") (pin "108") (pinfunction "VDD_108") (pintype "passive"))
      (node (ref "U1") (pin "121") (pinfunction "VDD_121") (pintype "passive"))
      (node (ref "U1") (pin "131") (pinfunction "VDD_131") (pintype "passive"))
      (node (ref "U1") (pin "143") (pinfunction "PDR_ON_143") (pintype "passive"))
      (node (ref "U1") (pin "144") (pinfunction "VDD_144") (pintype "passive"))
      (node (ref "U1") (pin "17") (pinfunction "VDD_17") (pintype "passive"))
      (node (ref "U1") (pin "30") (pinfunction "VDD_30") (pintype "passive"))
      (node (ref "U1") (pin "39") (pinfunction "VDD_39") (pintype "passive"))
      (node (ref "U1") (pin "52") (pinfunction "VDD_52") (pintype "passive"))
      (node (ref "U1") (pin "62") (pinfunction "VDD_62") (pintype "passive"))
      (node (ref "U1") (pin "72") (pinfunction "VDD_72") (pintype "passive"))
      (node (ref "U1") (pin "84") (pinfunction "VDD_84") (pintype "passive"))
      (node (ref "U1") (pin "95") (pinfunction "VDD_95") (pintype "passive"))
    )
  )
)
